# RC_Transmitter_Backend.net
KiCad netlist of a schematic drawn in Altium Designer
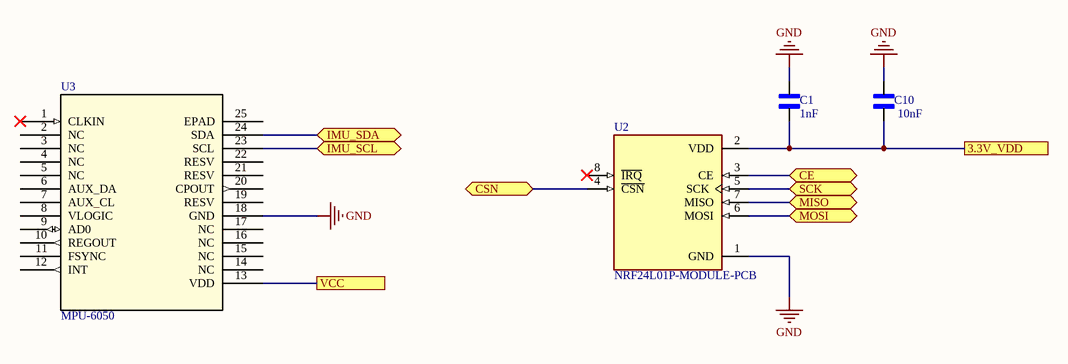
[diagram p0: RC Transmitter Backend.SchDoc]

(export (version "E")
  (design (tool "Eeschema 10.0.6"))
  (components
    (comp (ref "C1")
      (value "1nF")
      (footprint "CAPC1005X55N")
      (fields (field (name "MF") "Murata Electronics") (field (name "MP") "GRM155R61A102KA01D"))
      (libsource (lib "GRM155R61A102KA01D") (part "GRM155R61A102KA01D"))
    )
    (comp (ref "C10")
      (value "10nF")
      (footprint "CAPC0603X33N")
      (description "10000 pF Â±10% 10V Ceramic Capacitor X7R 0201 (0603 Metric)")
      (fields (field (name "MF") "Murata") (field (name "MP") "GRM033R71A103KA01D"))
      (libsource (lib "GRM033R71A103KA01D") (part "GRM033R71A103KA01D"))
    )
    (comp (ref "U2")
      (value "NRF24L01P-MODULE-PCB")
      (footprint "XCVR_NRF24L01P-MODULE-PCB")
      (description "- Transceiver For Use With nRF24L01+")
      (fields (field (name "MF") "Nordic Semiconductor"))
      (libsource (lib "NRF24L01P-MODULE-PCB") (part "NRF24L01P-MODULE-PCB"))
    )
    (comp (ref "U3")
      (value "MPU-6050")
      (footprint "QFN24_4X4X0P9-0P5_TDK-L")
      (description "Description")
      (fields (field (name "COPYRIGHT") "Copyright (C) 2025 Ultra Librarian. All rights reserved."))
      (libsource (lib "MPU-6050") (part "MPU-6050"))
    )
  )
  (nets
    (net (code "1") (name "/3.3V_VDD") (class "Default")
      (node (ref "C1") (pin "1") (pinfunction "1_1") (pintype "passive"))
      (node (ref "C10") (pin "1") (pinfunction "1_1") (pintype "passive"))
      (node (ref "U2") (pin "2") (pinfunction "VDD_2") (pintype "power_in"))
    )
    (net (code "2") (name "/CE") (class "Default")
      (node (ref "U2") (pin "3") (pinfunction "CE_3") (pintype "input"))
    )
    (net (code "3") (name "/CSN") (class "Default")
      (node (ref "U2") (pin "4") (pinfunction "~{CSN}_4") (pintype "input"))
    )
    (net (code "4") (name "/IMU_SCL") (class "Default")
      (node (ref "U3") (pin "23") (pinfunction "SCL_23") (pintype "passive"))
    )
    (net (code "5") (name "/IMU_SDA") (class "Default")
      (node (ref "U3") (pin "24") (pinfunction "SDA_24") (pintype "passive"))
    )
    (net (code "6") (name "/MISO") (class "Default")
      (node (ref "U2") (pin "7") (pinfunction "MISO_7") (pintype "input"))
    )
    (net (code "7") (name "/MOSI") (class "Default")
      (node (ref "U2") (pin "6") (pinfunction "MOSI_6") (pintype "input"))
    )
    (net (code "8") (name "/SCK") (class "Default")
      (node (ref "U2") (pin "5") (pinfunction "SCK_5") (pintype "input"))
    )
    (net (code "9") (name "/VCC") (class "Default")
      (node (ref "U3") (pin "13") (pinfunction "VDD_13") (pintype "power_in"))
    )
    (net (code "10") (name "GND") (class "Default")
      (node (ref "C1") (pin "2") (pinfunction "2_2") (pintype "passive"))
      (node (ref "C10") (pin "2") (pinfunction "2_2") (pintype "passive"))
      (node (ref "U2") (pin "1") (pinfunction "GND_1") (pintype "power_in"))
      (node (ref "U3") (pin "18") (pinfunction "GND_18") (pintype "power_in"))
    )
    (net (code "11") (name "unconnected-(U2-~{IRQ}-Pad8)") (class "Default")
      (node (ref "U2") (pin "8") (pinfunction "~{IRQ}_8") (pintype "input+no_connect"))
    )
    (net (code "12") (name "unconnected-(U3-AD0-Pad9)") (class "Default")
      (node (ref "U3") (pin "9") (pinfunction "AD0_9") (pintype "bidirectional"))
    )
    (net (code "13") (name "unconnected-(U3-AUX_CL-Pad7)") (class "Default")
      (node (ref "U3") (pin "7") (pinfunction "AUX_CL_7") (pintype "passive"))
    )
    (net (code "14") (name "unconnected-(U3-AUX_DA-Pad6)") (class "Default")
      (node (ref "U3") (pin "6") (pinfunction "AUX_DA_6") (pintype "passive"))
    )
    (net (code "15") (name "unconnected-(U3-CLKIN-Pad1)") (class "Default")
      (node (ref "U3") (pin "1") (pinfunction "CLKIN_1") (pintype "input+no_connect"))
    )
    (net (code "16") (name "unconnected-(U3-CPOUT-Pad20)") (class "Default")
      (node (ref "U3") (pin "20") (pinfunction "CPOUT_20") (pintype "output"))
    )
    (net (code "17") (name "unconnected-(U3-EPAD-Pad25)") (class "Default")
      (node (ref "U3") (pin "25") (pinfunction "EPAD_25") (pintype "passive"))
    )
    (net (code "18") (name "unconnected-(U3-FSYNC-Pad11)") (class "Default")
      (node (ref "U3") (pin "11") (pinfunction "FSYNC_11") (pintype "passive"))
    )
    (net (code "19") (name "unconnected-(U3-INT-Pad12)") (class "Default")
      (node (ref "U3") (pin "12") (pinfunction "INT_12") (pintype "output"))
    )
    (net (code "20") (name "unconnected-(U3-NC-Pad2)") (class "Default")
      (node (ref "U3") (pin "2") (pinfunction "NC_2") (pintype "passive"))
    )
    (net (code "21") (name "unconnected-(U3-NC-Pad3)") (class "Default")
      (node (ref "U3") (pin "3") (pinfunction "NC_3") (pintype "passive"))
    )
    (net (code "22") (name "unconnected-(U3-NC-Pad4)") (class "Default")
      (node (ref "U3") (pin "4") (pinfunction "NC_4") (pintype "passive"))
    )
    (net (code "23") (name "unconnected-(U3-NC-Pad5)") (class "Default")
      (node (ref "U3") (pin "5") (pinfunction "NC_5") (pintype "passive"))
    )
    (net (code "24") (name "unconnected-(U3-NC-Pad14)") (class "Default")
      (node (ref "U3") (pin "14") (pinfunction "NC_14") (pintype "passive"))
    )
    (net (code "25") (name "unconnected-(U3-NC-Pad15)") (class "Default")
      (node (ref "U3") (pin "15") (pinfunction "NC_15") (pintype "passive"))
    )
    (net (code "26") (name "unconnected-(U3-NC-Pad16)") (class "Default")
      (node (ref "U3") (pin "16") (pinfunction "NC_16") (pintype "passive"))
    )
    (net (code "27") (name "unconnected-(U3-NC-Pad17)") (class "Default")
      (node (ref "U3") (pin "17") (pinfunction "NC_17") (pintype "passive"))
    )
    (net (code "28") (name "unconnected-(U3-REGOUT-Pad10)") (class "Default")
      (node (ref "U3") (pin "10") (pinfunction "REGOUT_10") (pintype "output"))
    )
    (net (code "29") (name "unconnected-(U3-RESV-Pad19)") (class "Default")
      (node (ref "U3") (pin "19") (pinfunction "RESV_19") (pintype "passive"))
    )
    (net (code "30") (name "unconnected-(U3-RESV-Pad21)") (class "Default")
      (node (ref "U3") (pin "21") (pinfunction "RESV_21") (pintype "passive"))
    )
    (net (code "31") (name "unconnected-(U3-RESV-Pad22)") (class "Default")
      (node (ref "U3") (pin "22") (pinfunction "RESV_22") (pintype "passive"))
    )
    (net (code "32") (name "unconnected-(U3-VLOGIC-Pad8)") (class "Default")
      (node (ref "U3") (pin "8") (pinfunction "VLOGIC_8") (pintype "power_in"))
    )
  )
)
